# avr-node.net
KiCad netlist of a schematic drawn in EAGLE
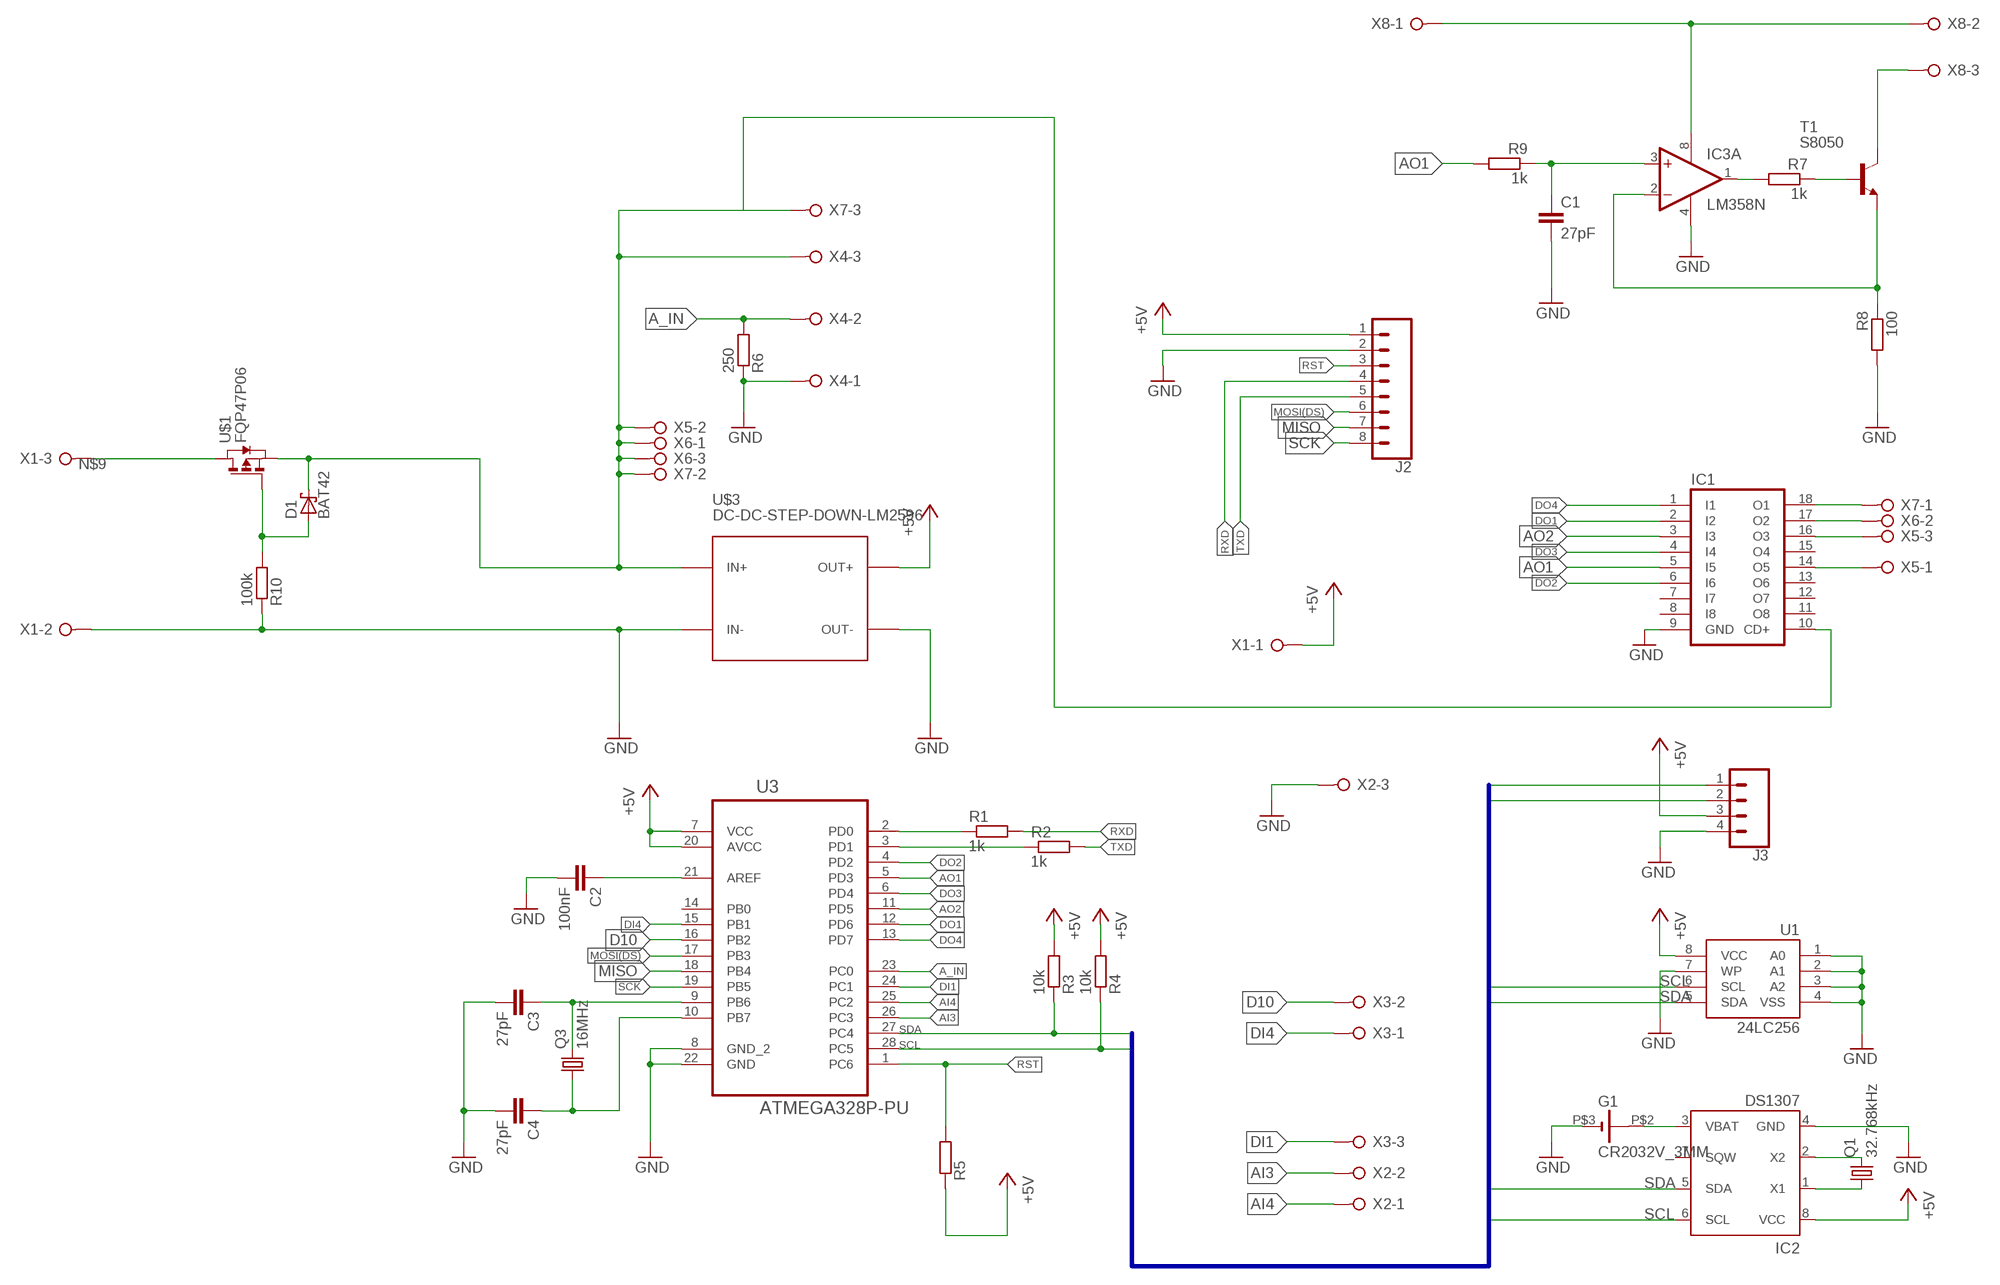
[diagram p0: schematic, sheet 1]

(export (version "E")
  (design (tool "Eeschema 10.0.6"))
  (components
    (comp (ref "C1")
      (value "27pF")
      (footprint "eagle-import:C050-025X075")
      (libsource (lib "eagle-import") (part "C-EU050-025X075"))
    )
    (comp (ref "C2")
      (value "100nF")
      (footprint "eagle-import:C050-025X075")
      (libsource (lib "eagle-import") (part "C-EU050-025X075"))
    )
    (comp (ref "C3")
      (value "27pF")
      (footprint "eagle-import:C050-025X075")
      (libsource (lib "eagle-import") (part "C-EU050-025X075"))
    )
    (comp (ref "C4")
      (value "27pF")
      (footprint "eagle-import:C050-025X075")
      (libsource (lib "eagle-import") (part "C-EU050-025X075"))
    )
    (comp (ref "D1")
      (value "BAT42")
      (footprint "eagle-import:DO35-10")
      (libsource (lib "eagle-import") (part "BAT42"))
    )
    (comp (ref "G1")
      (value "CR2032V_3MM")
      (footprint "eagle-import:CR2032V_3MM")
      (libsource (lib "eagle-import") (part "CR2032V_3MM"))
    )
    (comp (ref "IC1")
      (value "ULN2803A")
      (footprint "eagle-import:DIL18")
      (libsource (lib "eagle-import") (part "ULN2803A"))
    )
    (comp (ref "IC2")
      (value "DS1307")
      (footprint "eagle-import:DIL08")
      (libsource (lib "eagle-import") (part "DS1307"))
    )
    (comp (ref "IC3")
      (value "LM358N")
      (footprint "eagle-import:DIL08")
      (libsource (lib "eagle-import") (part "LM358N"))
    )
    (comp (ref "J2")
      (value "CONN_08LONGPADS")
      (footprint "eagle-import:1X08_LONGPADS")
      (libsource (lib "eagle-import") (part "CONN_08LONGPADS"))
    )
    (comp (ref "J3")
      (value "CONN_04PTH")
      (footprint "eagle-import:1X04")
      (libsource (lib "eagle-import") (part "CONN_04PTH"))
    )
    (comp (ref "Q1")
      (value "32.768kHz")
      (footprint "eagle-import:TC26V")
      (libsource (lib "eagle-import") (part "CRYSTALTC26V"))
    )
    (comp (ref "Q3")
      (value "16MHz")
      (footprint "eagle-import:HC49U-V")
      (libsource (lib "eagle-import") (part "crystal_CRYSTALHC49U-V"))
    )
    (comp (ref "R1")
      (value "1k")
      (footprint "eagle-import:0204_7")
      (libsource (lib "eagle-import") (part "R-EU_0204/7"))
    )
    (comp (ref "R2")
      (value "1k")
      (footprint "eagle-import:0204_7")
      (libsource (lib "eagle-import") (part "R-EU_0204/7"))
    )
    (comp (ref "R3")
      (value "10k")
      (footprint "eagle-import:0204_7")
      (libsource (lib "eagle-import") (part "R-EU_0204/7"))
    )
    (comp (ref "R4")
      (value "10k")
      (footprint "eagle-import:0204_7")
      (libsource (lib "eagle-import") (part "R-EU_0204/7"))
    )
    (comp (ref "R5")
      (value "R-EU_0204/7")
      (footprint "eagle-import:0204_7")
      (libsource (lib "eagle-import") (part "R-EU_0204/7"))
    )
    (comp (ref "R6")
      (value "250")
      (footprint "eagle-import:0204_7")
      (libsource (lib "eagle-import") (part "R-EU_0204/7"))
    )
    (comp (ref "R7")
      (value "1k")
      (footprint "eagle-import:0204_7")
      (libsource (lib "eagle-import") (part "R-EU_0204/7"))
    )
    (comp (ref "R8")
      (value "100")
      (footprint "eagle-import:0204_7")
      (libsource (lib "eagle-import") (part "R-EU_0204/7"))
    )
    (comp (ref "R9")
      (value "1k")
      (footprint "eagle-import:0204_7")
      (libsource (lib "eagle-import") (part "R-EU_0204/7"))
    )
    (comp (ref "R10")
      (value "100k")
      (footprint "eagle-import:0204_7")
      (libsource (lib "eagle-import") (part "R-EU_0204/7"))
    )
    (comp (ref "T1")
      (value "S8050")
      (footprint "eagle-import:TO92L")
      (libsource (lib "eagle-import") (part "-NPN-TO92L"))
    )
    (comp (ref "U$1")
      (value "FQP47P06")
      (footprint "eagle-import:TO220")
      (libsource (lib "eagle-import") (part "FQP47P06"))
    )
    (comp (ref "U$3")
      (value "DC-DC-STEP-DOWN-LM2596")
      (footprint "eagle-import:DC-DC-STEP-DOWN-LM2596")
      (libsource (lib "eagle-import") (part "DC-DC-STEP-DOWN-LM2596"))
    )
    (comp (ref "U1")
      (value "24LC256")
      (footprint "eagle-import:SO08")
      (libsource (lib "eagle-import") (part "EEPROM-I2CSMD"))
    )
    (comp (ref "U3")
      (value "ATMEGA328P-PU")
      (footprint "eagle-import:DIP254P762X457-28")
      (libsource (lib "eagle-import") (part "ATMEGA328P-PU"))
    )
    (comp (ref "X1")
      (value "W237-3E")
      (footprint "eagle-import:W237-3E")
      (libsource (lib "eagle-import") (part "W237-3E"))
    )
    (comp (ref "X2")
      (value "W237-3E")
      (footprint "eagle-import:W237-3E")
      (libsource (lib "eagle-import") (part "W237-3E"))
    )
    (comp (ref "X3")
      (value "W237-3E")
      (footprint "eagle-import:W237-3E")
      (libsource (lib "eagle-import") (part "W237-3E"))
    )
    (comp (ref "X4")
      (value "W237-3E")
      (footprint "eagle-import:W237-3E")
      (libsource (lib "eagle-import") (part "W237-3E"))
    )
    (comp (ref "X5")
      (value "W237-3E")
      (footprint "eagle-import:W237-3E")
      (libsource (lib "eagle-import") (part "W237-3E"))
    )
    (comp (ref "X6")
      (value "W237-3E")
      (footprint "eagle-import:W237-3E")
      (libsource (lib "eagle-import") (part "W237-3E"))
    )
    (comp (ref "X7")
      (value "W237-3E")
      (footprint "eagle-import:W237-3E")
      (libsource (lib "eagle-import") (part "W237-3E"))
    )
    (comp (ref "X8")
      (value "W237-3E")
      (footprint "eagle-import:W237-3E")
      (libsource (lib "eagle-import") (part "W237-3E"))
    )
  )
  (nets
    (net (code "1") (name "+5V") (class "Default")
      (node (ref "IC2") (pin "8") (pinfunction "VCC_8") (pintype "power_in"))
      (node (ref "J2") (pin "1") (pinfunction "1_1") (pintype "passive"))
      (node (ref "J3") (pin "3") (pinfunction "3_3") (pintype "passive"))
      (node (ref "R3") (pin "2") (pinfunction "2_2") (pintype "passive"))
      (node (ref "R4") (pin "2") (pinfunction "2_2") (pintype "passive"))
      (node (ref "R5") (pin "1") (pinfunction "1_1") (pintype "passive"))
      (node (ref "U$3") (pin "OUT+") (pinfunction "OUT+_OUT+") (pintype "bidirectional"))
      (node (ref "U1") (pin "8") (pinfunction "VCC_8") (pintype "power_in"))
      (node (ref "U3") (pin "20") (pinfunction "AVCC_20") (pintype "power_in"))
      (node (ref "U3") (pin "7") (pinfunction "VCC_7") (pintype "power_in"))
      (node (ref "X1") (pin "1") (pinfunction "KL_1") (pintype "passive"))
    )
    (net (code "2") (name "/N$9") (class "Default")
      (node (ref "U$1") (pin "2") (pinfunction "D_2") (pintype "passive"))
      (node (ref "X1") (pin "3") (pinfunction "KL_3") (pintype "passive"))
    )
    (net (code "3") (name "/SCL") (class "Default")
      (node (ref "IC2") (pin "6") (pinfunction "SCL_6") (pintype "input"))
      (node (ref "J3") (pin "1") (pinfunction "1_1") (pintype "passive"))
      (node (ref "R4") (pin "1") (pinfunction "1_1") (pintype "passive"))
      (node (ref "U1") (pin "6") (pinfunction "SCL_6") (pintype "bidirectional"))
      (node (ref "U3") (pin "28") (pinfunction "PC5_28") (pintype "bidirectional"))
    )
    (net (code "4") (name "/SDA") (class "Default")
      (node (ref "IC2") (pin "5") (pinfunction "SDA_5") (pintype "bidirectional"))
      (node (ref "J3") (pin "2") (pinfunction "2_2") (pintype "passive"))
      (node (ref "R3") (pin "1") (pinfunction "1_1") (pintype "passive"))
      (node (ref "U1") (pin "5") (pinfunction "SDA_5") (pintype "bidirectional"))
      (node (ref "U3") (pin "27") (pinfunction "PC4_27") (pintype "bidirectional"))
    )
    (net (code "5") (name "AI3") (class "Default")
      (node (ref "U3") (pin "26") (pinfunction "PC3_26") (pintype "bidirectional"))
      (node (ref "X2") (pin "2") (pinfunction "KL_2") (pintype "passive"))
    )
    (net (code "6") (name "AI4") (class "Default")
      (node (ref "U3") (pin "25") (pinfunction "PC2_25") (pintype "bidirectional"))
      (node (ref "X2") (pin "1") (pinfunction "KL_1") (pintype "passive"))
    )
    (net (code "7") (name "AO1") (class "Default")
      (node (ref "IC1") (pin "5") (pinfunction "I5_5") (pintype "input"))
      (node (ref "R9") (pin "2") (pinfunction "2_2") (pintype "passive"))
      (node (ref "U3") (pin "5") (pinfunction "PD3_5") (pintype "bidirectional"))
    )
    (net (code "8") (name "AO2") (class "Default")
      (node (ref "IC1") (pin "3") (pinfunction "I3_3") (pintype "input"))
      (node (ref "U3") (pin "11") (pinfunction "PD5_11") (pintype "bidirectional"))
    )
    (net (code "9") (name "A_IN") (class "Default")
      (node (ref "R6") (pin "2") (pinfunction "2_2") (pintype "passive"))
      (node (ref "U3") (pin "23") (pinfunction "PC0_23") (pintype "bidirectional"))
      (node (ref "X4") (pin "2") (pinfunction "KL_2") (pintype "passive"))
    )
    (net (code "10") (name "D10") (class "Default")
      (node (ref "U3") (pin "16") (pinfunction "PB2_16") (pintype "bidirectional"))
      (node (ref "X3") (pin "2") (pinfunction "KL_2") (pintype "passive"))
    )
    (net (code "11") (name "DI1") (class "Default")
      (node (ref "U3") (pin "24") (pinfunction "PC1_24") (pintype "bidirectional"))
      (node (ref "X3") (pin "3") (pinfunction "KL_3") (pintype "passive"))
    )
    (net (code "12") (name "DI4") (class "Default")
      (node (ref "U3") (pin "15") (pinfunction "PB1_15") (pintype "bidirectional"))
      (node (ref "X3") (pin "1") (pinfunction "KL_1") (pintype "passive"))
    )
    (net (code "13") (name "DO1") (class "Default")
      (node (ref "IC1") (pin "2") (pinfunction "I2_2") (pintype "input"))
      (node (ref "U3") (pin "12") (pinfunction "PD6_12") (pintype "bidirectional"))
    )
    (net (code "14") (name "DO2") (class "Default")
      (node (ref "IC1") (pin "6") (pinfunction "I6_6") (pintype "input"))
      (node (ref "U3") (pin "4") (pinfunction "PD2_4") (pintype "bidirectional"))
    )
    (net (code "15") (name "DO3") (class "Default")
      (node (ref "IC1") (pin "4") (pinfunction "I4_4") (pintype "input"))
      (node (ref "U3") (pin "6") (pinfunction "PD4_6") (pintype "bidirectional"))
    )
    (net (code "16") (name "DO4") (class "Default")
      (node (ref "IC1") (pin "1") (pinfunction "I1_1") (pintype "input"))
      (node (ref "U3") (pin "13") (pinfunction "PD7_13") (pintype "bidirectional"))
    )
    (net (code "17") (name "GND") (class "Default")
      (node (ref "C1") (pin "2") (pinfunction "2_2") (pintype "passive"))
      (node (ref "C2") (pin "2") (pinfunction "2_2") (pintype "passive"))
      (node (ref "C3") (pin "2") (pinfunction "2_2") (pintype "passive"))
      (node (ref "C4") (pin "2") (pinfunction "2_2") (pintype "passive"))
      (node (ref "G1") (pin "P$3") (pinfunction "-_P$3") (pintype "passive"))
      (node (ref "IC1") (pin "9") (pinfunction "GND_9") (pintype "power_in"))
      (node (ref "IC2") (pin "4") (pinfunction "GND_4") (pintype "power_in"))
      (node (ref "IC3") (pin "4") (pinfunction "V-_4") (pintype "power_in"))
      (node (ref "J2") (pin "2") (pinfunction "2_2") (pintype "passive"))
      (node (ref "J3") (pin "4") (pinfunction "4_4") (pintype "passive"))
      (node (ref "R10") (pin "1") (pinfunction "1_1") (pintype "passive"))
      (node (ref "R6") (pin "1") (pinfunction "1_1") (pintype "passive"))
      (node (ref "R8") (pin "2") (pinfunction "2_2") (pintype "passive"))
      (node (ref "U$3") (pin "IN-") (pinfunction "IN-_IN-") (pintype "bidirectional"))
      (node (ref "U$3") (pin "OUT-") (pinfunction "OUT-_OUT-") (pintype "bidirectional"))
      (node (ref "U1") (pin "1") (pinfunction "A0_1") (pintype "bidirectional"))
      (node (ref "U1") (pin "2") (pinfunction "A1_2") (pintype "bidirectional"))
      (node (ref "U1") (pin "3") (pinfunction "A2_3") (pintype "bidirectional"))
      (node (ref "U1") (pin "4") (pinfunction "VSS_4") (pintype "power_in"))
      (node (ref "U1") (pin "7") (pinfunction "WP_7") (pintype "bidirectional"))
      (node (ref "U3") (pin "22") (pinfunction "GND_22") (pintype "passive"))
      (node (ref "U3") (pin "8") (pinfunction "GND_2_8") (pintype "passive"))
      (node (ref "X1") (pin "2") (pinfunction "KL_2") (pintype "passive"))
      (node (ref "X2") (pin "3") (pinfunction "KL_3") (pintype "passive"))
      (node (ref "X4") (pin "1") (pinfunction "KL_1") (pintype "passive"))
    )
    (net (code "18") (name "MISO") (class "Default")
      (node (ref "J2") (pin "7") (pinfunction "7_7") (pintype "passive"))
      (node (ref "U3") (pin "18") (pinfunction "PB4_18") (pintype "bidirectional"))
    )
    (net (code "19") (name "MOSI(DS)") (class "Default")
      (node (ref "J2") (pin "6") (pinfunction "6_6") (pintype "passive"))
      (node (ref "U3") (pin "17") (pinfunction "PB3_17") (pintype "bidirectional"))
    )
    (net (code "20") (name "Net-(IC1-CD+)") (class "Default")
      (node (ref "D1") (pin "C") (pinfunction "C_C") (pintype "passive"))
      (node (ref "IC1") (pin "10") (pinfunction "CD+_10") (pintype "passive"))
      (node (ref "U$1") (pin "3") (pinfunction "S_3") (pintype "passive"))
      (node (ref "U$3") (pin "IN+") (pinfunction "IN+_IN+") (pintype "bidirectional"))
      (node (ref "X4") (pin "3") (pinfunction "KL_3") (pintype "passive"))
      (node (ref "X5") (pin "2") (pinfunction "KL_2") (pintype "passive"))
      (node (ref "X6") (pin "1") (pinfunction "KL_1") (pintype "passive"))
      (node (ref "X6") (pin "3") (pinfunction "KL_3") (pintype "passive"))
      (node (ref "X7") (pin "2") (pinfunction "KL_2") (pintype "passive"))
      (node (ref "X7") (pin "3") (pinfunction "KL_3") (pintype "passive"))
    )
    (net (code "21") (name "Net-(IC1-O1)") (class "Default")
      (node (ref "IC1") (pin "18") (pinfunction "O1_18") (pintype "open_collector"))
      (node (ref "X7") (pin "1") (pinfunction "KL_1") (pintype "passive"))
    )
    (net (code "22") (name "Net-(IC1-O2)") (class "Default")
      (node (ref "IC1") (pin "17") (pinfunction "O2_17") (pintype "open_collector"))
      (node (ref "X6") (pin "2") (pinfunction "KL_2") (pintype "passive"))
    )
    (net (code "23") (name "Net-(IC1-O3)") (class "Default")
      (node (ref "IC1") (pin "16") (pinfunction "O3_16") (pintype "open_collector"))
      (node (ref "X5") (pin "3") (pinfunction "KL_3") (pintype "passive"))
    )
    (net (code "24") (name "Net-(IC1-O5)") (class "Default")
      (node (ref "IC1") (pin "14") (pinfunction "O5_14") (pintype "open_collector"))
      (node (ref "X5") (pin "1") (pinfunction "KL_1") (pintype "passive"))
    )
    (net (code "25") (name "Net-(IC2-VBAT)") (class "Default")
      (node (ref "G1") (pin "P$2") (pinfunction "+_P$2") (pintype "passive"))
      (node (ref "IC2") (pin "3") (pinfunction "VBAT_3") (pintype "passive"))
    )
    (net (code "26") (name "Net-(IC2-X1)") (class "Default")
      (node (ref "IC2") (pin "1") (pinfunction "X1_1") (pintype "input"))
      (node (ref "Q1") (pin "1") (pinfunction "1_1") (pintype "passive"))
    )
    (net (code "27") (name "Net-(IC2-X2)") (class "Default")
      (node (ref "IC2") (pin "2") (pinfunction "X2_2") (pintype "output"))
      (node (ref "Q1") (pin "2") (pinfunction "2_2") (pintype "passive"))
    )
    (net (code "28") (name "Net-(IC3A-+IN)") (class "Default")
      (node (ref "C1") (pin "1") (pinfunction "1_1") (pintype "passive"))
      (node (ref "IC3") (pin "3") (pinfunction "+IN_3") (pintype "input"))
      (node (ref "R9") (pin "1") (pinfunction "1_1") (pintype "passive"))
    )
    (net (code "29") (name "Net-(IC3A--IN)") (class "Default")
      (node (ref "IC3") (pin "2") (pinfunction "-IN_2") (pintype "input"))
      (node (ref "R8") (pin "1") (pinfunction "1_1") (pintype "passive"))
      (node (ref "T1") (pin "1") (pinfunction "E_1") (pintype "passive"))
    )
    (net (code "30") (name "Net-(IC3A-OUT)") (class "Default")
      (node (ref "IC3") (pin "1") (pinfunction "OUT_1") (pintype "output"))
      (node (ref "R7") (pin "2") (pinfunction "2_2") (pintype "passive"))
    )
    (net (code "31") (name "Net-(IC3C-V+)") (class "Default")
      (node (ref "IC3") (pin "8") (pinfunction "V+_8") (pintype "power_in"))
      (node (ref "X8") (pin "1") (pinfunction "KL_1") (pintype "passive"))
      (node (ref "X8") (pin "2") (pinfunction "KL_2") (pintype "passive"))
    )
    (net (code "32") (name "Net-(T1-B)") (class "Default")
      (node (ref "R7") (pin "1") (pinfunction "1_1") (pintype "passive"))
      (node (ref "T1") (pin "2") (pinfunction "B_2") (pintype "passive"))
    )
    (net (code "33") (name "Net-(T1-C)") (class "Default")
      (node (ref "T1") (pin "3") (pinfunction "C_3") (pintype "passive"))
      (node (ref "X8") (pin "3") (pinfunction "KL_3") (pintype "passive"))
    )
    (net (code "34") (name "Net-(U$1-G)") (class "Default")
      (node (ref "D1") (pin "A") (pinfunction "A_A") (pintype "passive"))
      (node (ref "R10") (pin "2") (pinfunction "2_2") (pintype "passive"))
      (node (ref "U$1") (pin "1") (pinfunction "G_1") (pintype "passive"))
    )
    (net (code "35") (name "Net-(U3-AREF)") (class "Default")
      (node (ref "C2") (pin "1") (pinfunction "1_1") (pintype "passive"))
      (node (ref "U3") (pin "21") (pinfunction "AREF_21") (pintype "input"))
    )
    (net (code "36") (name "Net-(U3-PB6)") (class "Default")
      (node (ref "C3") (pin "1") (pinfunction "1_1") (pintype "passive"))
      (node (ref "Q3") (pin "2") (pinfunction "2_2") (pintype "passive"))
      (node (ref "U3") (pin "9") (pinfunction "PB6_9") (pintype "bidirectional"))
    )
    (net (code "37") (name "Net-(U3-PB7)") (class "Default")
      (node (ref "C4") (pin "1") (pinfunction "1_1") (pintype "passive"))
      (node (ref "Q3") (pin "1") (pinfunction "1_1") (pintype "passive"))
      (node (ref "U3") (pin "10") (pinfunction "PB7_10") (pintype "bidirectional"))
    )
    (net (code "38") (name "Net-(U3-PD0)") (class "Default")
      (node (ref "R1") (pin "1") (pinfunction "1_1") (pintype "passive"))
      (node (ref "U3") (pin "2") (pinfunction "PD0_2") (pintype "bidirectional"))
    )
    (net (code "39") (name "Net-(U3-PD1)") (class "Default")
      (node (ref "R2") (pin "1") (pinfunction "1_1") (pintype "passive"))
      (node (ref "U3") (pin "3") (pinfunction "PD1_3") (pintype "bidirectional"))
    )
    (net (code "40") (name "RST") (class "Default")
      (node (ref "J2") (pin "3") (pinfunction "3_3") (pintype "passive"))
      (node (ref "R5") (pin "2") (pinfunction "2_2") (pintype "passive"))
      (node (ref "U3") (pin "1") (pinfunction "PC6_1") (pintype "bidirectional"))
    )
    (net (code "41") (name "RXD") (class "Default")
      (node (ref "J2") (pin "4") (pinfunction "4_4") (pintype "passive"))
      (node (ref "R1") (pin "2") (pinfunction "2_2") (pintype "passive"))
    )
    (net (code "42") (name "SCK") (class "Default")
      (node (ref "J2") (pin "8") (pinfunction "8_8") (pintype "passive"))
      (node (ref "U3") (pin "19") (pinfunction "PB5_19") (pintype "bidirectional"))
    )
    (net (code "43") (name "TXD") (class "Default")
      (node (ref "J2") (pin "5") (pinfunction "5_5") (pintype "passive"))
      (node (ref "R2") (pin "2") (pinfunction "2_2") (pintype "passive"))
    )
    (net (code "44") (name "unconnected-(G1-+-PadP$1)") (class "Default")
      (node (ref "G1") (pin "P$1") (pinfunction "+_P$1") (pintype "passive"))
    )
    (net (code "45") (name "unconnected-(IC1-I7-Pad7)") (class "Default")
      (node (ref "IC1") (pin "7") (pinfunction "I7_7") (pintype "input"))
    )
    (net (code "46") (name "unconnected-(IC1-I8-Pad8)") (class "Default")
      (node (ref "IC1") (pin "8") (pinfunction "I8_8") (pintype "input"))
    )
    (net (code "47") (name "unconnected-(IC1-O4-Pad15)") (class "Default")
      (node (ref "IC1") (pin "15") (pinfunction "O4_15") (pintype "open_collector"))
    )
    (net (code "48") (name "unconnected-(IC1-O6-Pad13)") (class "Default")
      (node (ref "IC1") (pin "13") (pinfunction "O6_13") (pintype "open_collector"))
    )
    (net (code "49") (name "unconnected-(IC1-O7-Pad12)") (class "Default")
      (node (ref "IC1") (pin "12") (pinfunction "O7_12") (pintype "open_collector"))
    )
    (net (code "50") (name "unconnected-(IC1-O8-Pad11)") (class "Default")
      (node (ref "IC1") (pin "11") (pinfunction "O8_11") (pintype "open_collector"))
    )
    (net (code "51") (name "unconnected-(IC2-SQW-Pad7)") (class "Default")
      (node (ref "IC2") (pin "7") (pinfunction "SQW_7") (pintype "open_collector"))
    )
    (net (code "52") (name "unconnected-(U3-PB0-Pad14)") (class "Default")
      (node (ref "U3") (pin "14") (pinfunction "PB0_14") (pintype "bidirectional"))
    )
  )
)
